# FET_Gate_Drive_Breakout.net
KiCad netlist of a schematic drawn in Altium Designer
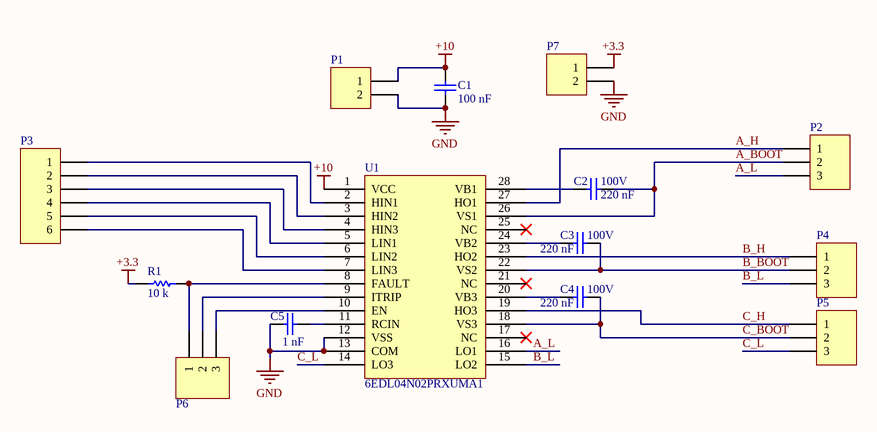
[diagram p0: FET_Gate_Drive_Breakout.SchDoc]

(export (version "E")
  (design (tool "Eeschema 10.0.6"))
  (components
    (comp (ref "C1")
      (value "100 nF")
      (footprint "0805 - Capacitor")
      (description "Nonpolarized Capacitor")
      (fields
        (field (name "MANUFACTURER") "Yageo")
        (field (name "MANUFACTURER PART NUMBER") "CC0805KRX7R9BB104")
      )
      (libsource (lib "General") (part "Capacitor - Nonpolarized"))
    )
    (comp (ref "C2")
      (value "220 nF")
      (footprint "0805 - Capacitor")
      (description "Nonpolarized Capacitor")
      (fields
        (field (name "MANUFACTURER") "Yageo")
        (field (name "RATING") "100V")
        (field (name "MANUFACTURER PART NUMBER") "CC0805KKX7R0BB224")
      )
      (libsource (lib "General") (part "Capacitor - Nonpolarized"))
    )
    (comp (ref "C3")
      (value "220 nF")
      (footprint "0805 - Capacitor")
      (description "Nonpolarized Capacitor")
      (fields
        (field (name "MANUFACTURER") "Yageo")
        (field (name "RATING") "100V")
        (field (name "MANUFACTURER PART NUMBER") "CC0805KKX7R0BB224")
      )
      (libsource (lib "General") (part "Capacitor - Nonpolarized"))
    )
    (comp (ref "C4")
      (value "220 nF")
      (footprint "0805 - Capacitor")
      (description "Nonpolarized Capacitor")
      (fields
        (field (name "MANUFACTURER") "Yageo")
        (field (name "RATING") "100V")
        (field (name "MANUFACTURER PART NUMBER") "CC0805KKX7R0BB224")
      )
      (libsource (lib "General") (part "Capacitor - Nonpolarized"))
    )
    (comp (ref "C5")
      (value "1 nF")
      (footprint "0805 - Capacitor")
      (description "Nonpolarized Capacitor")
      (fields
        (field (name "MANUFACTURER") "Yageo")
        (field (name "MANUFACTURER PART NUMBER") "CC0805KRX7R9BB102")
      )
      (libsource (lib "General") (part "Capacitor - Nonpolarized"))
    )
    (comp (ref "P1")
      (value "1x2 Header")
      (footprint "HDR1X2")
      (description "1x2 Pin Header")
      (libsource (lib "GeneralConnectors") (part "1x2 Header"))
    )
    (comp (ref "P2")
      (value "1x3 Header")
      (footprint "HDR1X3")
      (description "1x3 Pin Header")
      (libsource (lib "GeneralConnectors") (part "1x3 Header"))
    )
    (comp (ref "P3")
      (value "1x6 Header")
      (footprint "HDR1X6")
      (description "1x6 Pin Header")
      (libsource (lib "GeneralConnectors") (part "1x6 Header"))
    )
    (comp (ref "P4")
      (value "1x3 Header")
      (footprint "HDR1X3")
      (description "1x3 Pin Header")
      (libsource (lib "GeneralConnectors") (part "1x3 Header"))
    )
    (comp (ref "P5")
      (value "1x3 Header")
      (footprint "HDR1X3")
      (description "1x3 Pin Header")
      (libsource (lib "GeneralConnectors") (part "1x3 Header"))
    )
    (comp (ref "P6")
      (value "1x3 Header")
      (footprint "HDR1X3")
      (description "1x3 Pin Header")
      (libsource (lib "") (part "1x3 Header_1"))
    )
    (comp (ref "P7")
      (value "1x2 Header")
      (footprint "HDR1X2")
      (description "1x2 Pin Header")
      (libsource (lib "GeneralConnectors") (part "1x2 Header"))
    )
    (comp (ref "R1")
      (value "10 k")
      (footprint "0603 - Resistor")
      (description "Resistor")
      (fields (field (name "MANUFACTURER PART NUMBER") "ESR03EZPJ103") (field (name "MANUFACTURER") "ROHM"))
      (libsource (lib "General") (part "Resistor"))
    )
    (comp (ref "U1")
      (value "6EDL04N02PRXUMA1")
      (footprint "TSOP65P640X120-28N")
      (description "200V Three Phase Gate Driver")
      (fields
        (field (name "MANUFACTURER") "Infineon")
        (field (name "DIGIKEY PART NUMBER") "6EDL04N02PRXUMA1CT-ND")
      )
      (libsource (lib "MC") (part "6EDL04N02PRXUMA1"))
    )
  )
  (nets
    (net (code "1") (name "+3.3") (class "Default")
      (node (ref "P7") (pin "1") (pinfunction "1_1") (pintype "passive"))
      (node (ref "R1") (pin "2") (pinfunction "2_2") (pintype "passive"))
    )
    (net (code "2") (name "+10") (class "Default")
      (node (ref "C1") (pin "1") (pinfunction "1_1") (pintype "passive"))
      (node (ref "P1") (pin "1") (pinfunction "1_1") (pintype "passive"))
      (node (ref "U1") (pin "1") (pinfunction "VCC_1") (pintype "power_in"))
    )
    (net (code "3") (name "/A_BOOT") (class "Default")
      (node (ref "C2") (pin "2") (pinfunction "2_2") (pintype "passive"))
      (node (ref "P2") (pin "2") (pinfunction "2_2") (pintype "passive"))
      (node (ref "U1") (pin "26") (pinfunction "VS1_26") (pintype "passive"))
    )
    (net (code "4") (name "/A_H") (class "Default")
      (node (ref "P2") (pin "1") (pinfunction "1_1") (pintype "passive"))
      (node (ref "U1") (pin "27") (pinfunction "HO1_27") (pintype "passive"))
    )
    (net (code "5") (name "/A_L") (class "Default")
      (node (ref "P2") (pin "3") (pinfunction "3_3") (pintype "passive"))
      (node (ref "U1") (pin "16") (pinfunction "LO1_16") (pintype "passive"))
    )
    (net (code "6") (name "/B_BOOT") (class "Default")
      (node (ref "C3") (pin "2") (pinfunction "2_2") (pintype "passive"))
      (node (ref "P4") (pin "2") (pinfunction "2_2") (pintype "passive"))
      (node (ref "U1") (pin "22") (pinfunction "VS2_22") (pintype "passive"))
    )
    (net (code "7") (name "/B_H") (class "Default")
      (node (ref "P4") (pin "1") (pinfunction "1_1") (pintype "passive"))
      (node (ref "U1") (pin "23") (pinfunction "HO2_23") (pintype "passive"))
    )
    (net (code "8") (name "/B_L") (class "Default")
      (node (ref "P4") (pin "3") (pinfunction "3_3") (pintype "passive"))
      (node (ref "U1") (pin "15") (pinfunction "LO2_15") (pintype "passive"))
    )
    (net (code "9") (name "/C_BOOT") (class "Default")
      (node (ref "C4") (pin "2") (pinfunction "2_2") (pintype "passive"))
      (node (ref "P5") (pin "2") (pinfunction "2_2") (pintype "passive"))
      (node (ref "U1") (pin "18") (pinfunction "VS3_18") (pintype "passive"))
    )
    (net (code "10") (name "/C_H") (class "Default")
      (node (ref "P5") (pin "1") (pinfunction "1_1") (pintype "passive"))
      (node (ref "U1") (pin "19") (pinfunction "HO3_19") (pintype "passive"))
    )
    (net (code "11") (name "/C_L") (class "Default")
      (node (ref "P5") (pin "3") (pinfunction "3_3") (pintype "passive"))
      (node (ref "U1") (pin "14") (pinfunction "LO3_14") (pintype "passive"))
    )
    (net (code "12") (name "GND") (class "Default")
      (node (ref "C1") (pin "2") (pinfunction "2_2") (pintype "passive"))
      (node (ref "C5") (pin "1") (pinfunction "1_1") (pintype "passive"))
      (node (ref "P1") (pin "2") (pinfunction "2_2") (pintype "passive"))
      (node (ref "P7") (pin "2") (pinfunction "2_2") (pintype "passive"))
      (node (ref "U1") (pin "12") (pinfunction "VSS_12") (pintype "passive"))
      (node (ref "U1") (pin "13") (pinfunction "COM_13") (pintype "power_in"))
    )
    (net (code "13") (name "Net-(U1-EN)") (class "Default")
      (node (ref "P6") (pin "3") (pinfunction "3_3") (pintype "passive"))
      (node (ref "U1") (pin "10") (pinfunction "EN_10") (pintype "passive"))
    )
    (net (code "14") (name "Net-(U1-FAULT)") (class "Default")
      (node (ref "P6") (pin "1") (pinfunction "1_1") (pintype "passive"))
      (node (ref "R1") (pin "1") (pinfunction "1_1") (pintype "passive"))
      (node (ref "U1") (pin "8") (pinfunction "FAULT_8") (pintype "passive"))
    )
    (net (code "15") (name "Net-(U1-HIN1)") (class "Default")
      (node (ref "P3") (pin "1") (pinfunction "1_1") (pintype "passive"))
      (node (ref "U1") (pin "2") (pinfunction "HIN1_2") (pintype "passive"))
    )
    (net (code "16") (name "Net-(U1-HIN2)") (class "Default")
      (node (ref "P3") (pin "2") (pinfunction "2_2") (pintype "passive"))
      (node (ref "U1") (pin "3") (pinfunction "HIN2_3") (pintype "passive"))
    )
    (net (code "17") (name "Net-(U1-HIN3)") (class "Default")
      (node (ref "P3") (pin "3") (pinfunction "3_3") (pintype "passive"))
      (node (ref "U1") (pin "4") (pinfunction "HIN3_4") (pintype "passive"))
    )
    (net (code "18") (name "Net-(U1-ITRIP)") (class "Default")
      (node (ref "P6") (pin "2") (pinfunction "2_2") (pintype "passive"))
      (node (ref "U1") (pin "9") (pinfunction "ITRIP_9") (pintype "passive"))
    )
    (net (code "19") (name "Net-(U1-LIN1)") (class "Default")
      (node (ref "P3") (pin "4") (pinfunction "4_4") (pintype "passive"))
      (node (ref "U1") (pin "5") (pinfunction "LIN1_5") (pintype "passive"))
    )
    (net (code "20") (name "Net-(U1-LIN2)") (class "Default")
      (node (ref "P3") (pin "5") (pinfunction "5_5") (pintype "passive"))
      (node (ref "U1") (pin "6") (pinfunction "LIN2_6") (pintype "passive"))
    )
    (net (code "21") (name "Net-(U1-LIN3)") (class "Default")
      (node (ref "P3") (pin "6") (pinfunction "6_6") (pintype "passive"))
      (node (ref "U1") (pin "7") (pinfunction "LIN3_7") (pintype "passive"))
    )
    (net (code "22") (name "Net-(U1-RCIN)") (class "Default")
      (node (ref "C5") (pin "2") (pinfunction "2_2") (pintype "passive"))
      (node (ref "U1") (pin "11") (pinfunction "RCIN_11") (pintype "passive"))
    )
    (net (code "23") (name "Net-(U1-VB1)") (class "Default")
      (node (ref "C2") (pin "1") (pinfunction "1_1") (pintype "passive"))
      (node (ref "U1") (pin "28") (pinfunction "VB1_28") (pintype "passive"))
    )
    (net (code "24") (name "Net-(U1-VB2)") (class "Default")
      (node (ref "C3") (pin "1") (pinfunction "1_1") (pintype "passive"))
      (node (ref "U1") (pin "24") (pinfunction "VB2_24") (pintype "passive"))
    )
    (net (code "25") (name "Net-(U1-VB3)") (class "Default")
      (node (ref "C4") (pin "1") (pinfunction "1_1") (pintype "passive"))
      (node (ref "U1") (pin "20") (pinfunction "VB3_20") (pintype "passive"))
    )
    (net (code "26") (name "unconnected-(U1-NC-Pad17)") (class "Default")
      (node (ref "U1") (pin "17") (pinfunction "NC_17") (pintype "passive+no_connect"))
    )
    (net (code "27") (name "unconnected-(U1-NC-Pad21)") (class "Default")
      (node (ref "U1") (pin "21") (pinfunction "NC_21") (pintype "passive+no_connect"))
    )
    (net (code "28") (name "unconnected-(U1-NC-Pad25)") (class "Default")
      (node (ref "U1") (pin "25") (pinfunction "NC_25") (pintype "passive+no_connect"))
    )
  )
)
